# AIRZAI_BASE_BD_REVC_Sheet2.net
KiCad netlist of a schematic drawn in Altium Designer
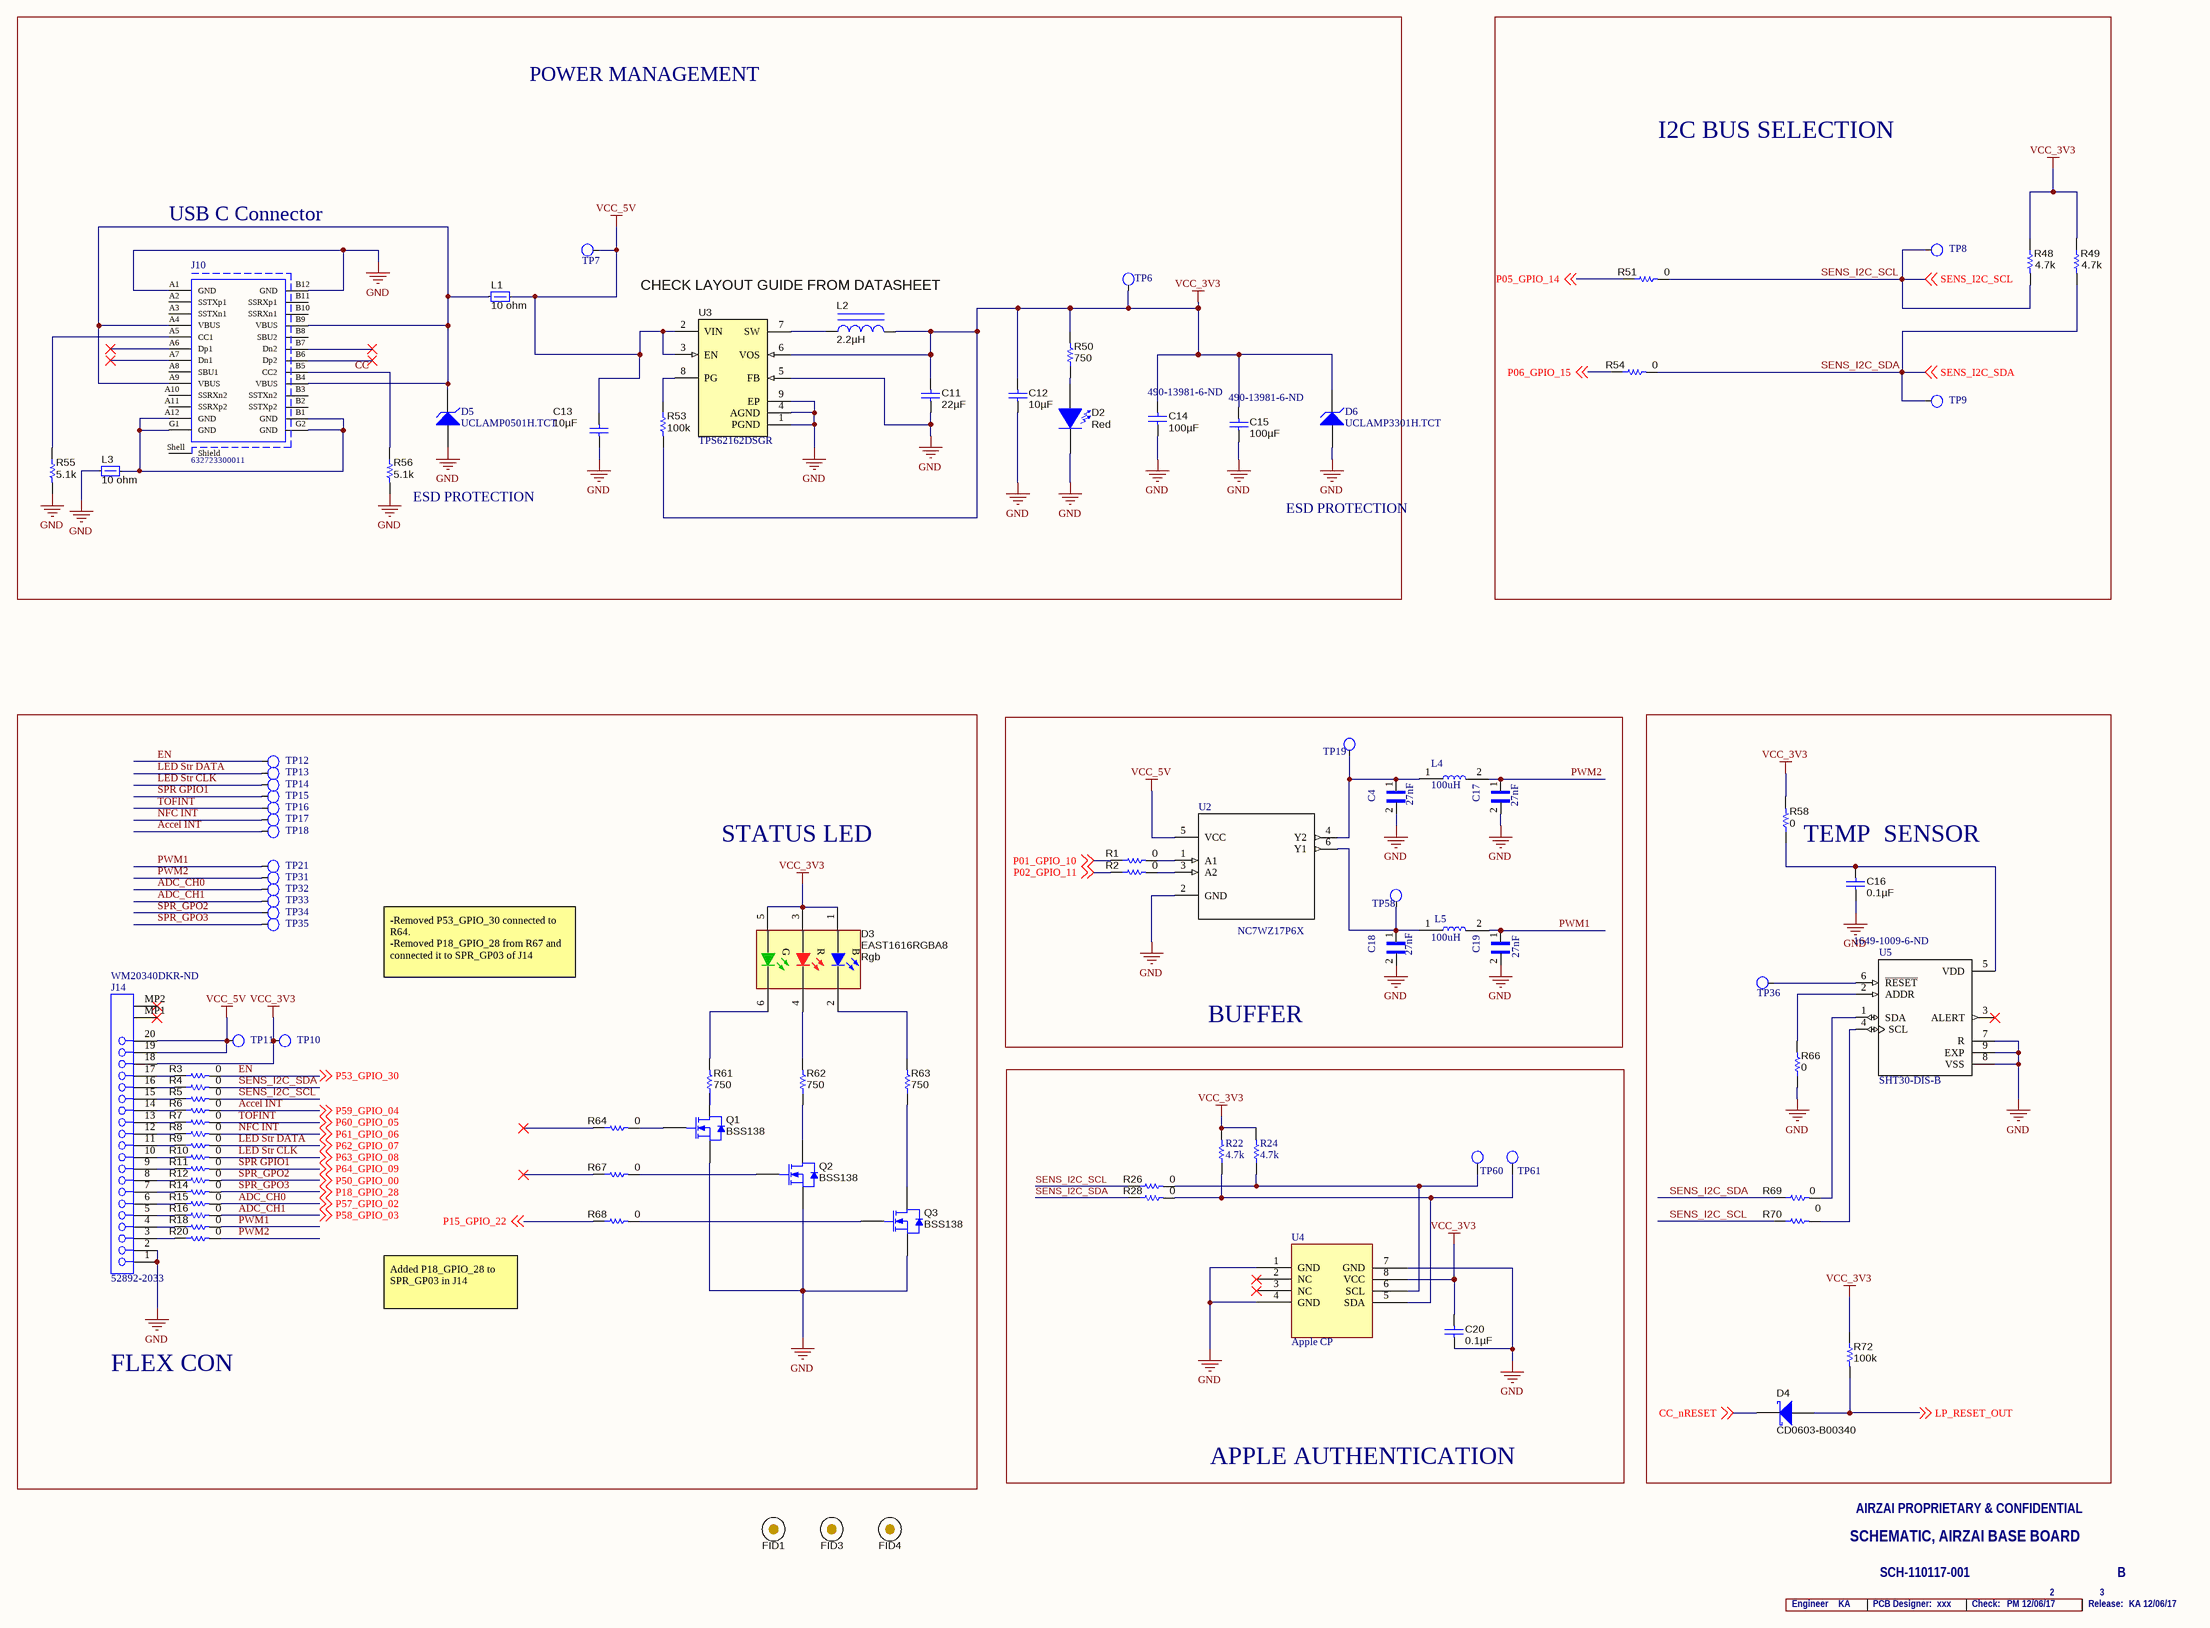
[diagram p0: AIRZAI_BASE_BD_REVC Sheet2.SchDoc]

(export (version "E")
  (design (tool "Eeschema 10.0.6"))
  (components
    (comp (ref "C4")
      (value "27nF")
      (footprint "1206CAP")
      (description "1206 27 nF 50 V Â±5% Tolerance C0G SMT Multilayer Ceramic Capacitor")
      (fields (field (name "MF") "Murata Electronics") (field (name "MP") "GRM3195C1H273JA01D"))
      (libsource (lib "GRM3195C1H273JA01D") (part "GRM3195C1H273JA01D"))
    )
    (comp (ref "C11")
      (value "C2012X5R1C226K125AC")
      (footprint "0805_HV")
      (description "CAP, CERM, 22 µF, 16 V, +/- 10%, X5R, 0805")
      (fields
        (field (name "VALUEDISPLAYED") "22µF")
        (field (name "MANUFACTURER") "TDK")
        (field (name "PUBLISHER") "Texas Instruments")
      )
      (libsource (lib "Capacitor_Ceramic") (part "C2012X5R1C226K125AC"))
    )
    (comp (ref "C12")
      (value "GRM21BR61A106KE19L")
      (footprint "0805_HV")
      (description "CAP, CERM, 10 µF, 10 V, +/- 10%, X5R, 0805")
      (fields
        (field (name "VALUEDISPLAYED") "10µF")
        (field (name "MANUFACTURER") "MuRata")
        (field (name "PUBLISHER") "Texas Instruments")
      )
      (libsource (lib "Capacitor_Ceramic") (part "GRM21BR61A106KE19L"))
    )
    (comp (ref "C13")
      (value "GRM21BR61A106KE19L")
      (footprint "0805_HV")
      (description "CAP, CERM, 10 µF, 10 V, +/- 10%, X5R, 0805")
      (fields
        (field (name "VALUEDISPLAYED") "10µF")
        (field (name "MANUFACTURER") "MuRata")
        (field (name "PUBLISHER") "Texas Instruments")
      )
      (libsource (lib "Capacitor_Ceramic") (part "GRM21BR61A106KE19L"))
    )
    (comp (ref "C14")
      (value "GRM31CR60J107ME39L")
      (footprint "1206_180")
      (description "CAP, CERM, 100 µF, 6.3 V, +/- 20%, X5R, 1206")
      (fields
        (field (name "VALUEDISPLAYED") "100µF")
        (field (name "MANUFACTURER") "MuRata")
        (field (name "SUPPLIER PART NUMBER 3") "490-13981-6-ND")
        (field (name "PUBLISHER") "Texas Instruments")
      )
      (libsource (lib "Capacitor_Ceramic") (part "GRM31CR60J107ME39L"))
    )
    (comp (ref "C15")
      (value "GRM31CR60J107ME39L")
      (footprint "1206_180")
      (description "CAP, CERM, 100 µF, 6.3 V, +/- 20%, X5R, 1206")
      (fields
        (field (name "VALUEDISPLAYED") "100µF")
        (field (name "MANUFACTURER") "MuRata")
        (field (name "SUPPLIER PART NUMBER 3") "490-13981-6-ND")
        (field (name "PUBLISHER") "Texas Instruments")
      )
      (libsource (lib "Capacitor_Ceramic") (part "GRM31CR60J107ME39L"))
    )
    (comp (ref "C16")
      (value "GRM155R61A104KA01D")
      (footprint "0402")
      (description "CAP, CERM, 0.1 µF, 10 V, +/- 10%, X5R, 0402")
      (fields
        (field (name "VALUEDISPLAYED") "0.1µF")
        (field (name "MANUFACTURER") "MuRata")
        (field (name "PUBLISHER") "Texas Instruments")
      )
      (libsource (lib "Capacitor_Ceramic") (part "GRM155R61A104KA01D"))
    )
    (comp (ref "C17")
      (value "27nF")
      (footprint "1206CAP")
      (description "1206 27 nF 50 V Â±5% Tolerance C0G SMT Multilayer Ceramic Capacitor")
      (fields (field (name "MF") "Murata Electronics") (field (name "MP") "GRM3195C1H273JA01D"))
      (libsource (lib "GRM3195C1H273JA01D") (part "GRM3195C1H273JA01D"))
    )
    (comp (ref "C18")
      (value "27nF")
      (footprint "1206CAP")
      (description "1206 27 nF 50 V Â±5% Tolerance C0G SMT Multilayer Ceramic Capacitor")
      (fields (field (name "MF") "Murata Electronics") (field (name "MP") "GRM3195C1H273JA01D"))
      (libsource (lib "GRM3195C1H273JA01D") (part "GRM3195C1H273JA01D"))
    )
    (comp (ref "C19")
      (value "27nF")
      (footprint "1206CAP")
      (description "1206 27 nF 50 V Â±5% Tolerance C0G SMT Multilayer Ceramic Capacitor")
      (fields (field (name "MF") "Murata Electronics") (field (name "MP") "GRM3195C1H273JA01D"))
      (libsource (lib "GRM3195C1H273JA01D") (part "GRM3195C1H273JA01D"))
    )
    (comp (ref "C20")
      (value "C1005X5R1A104K050BA")
      (footprint "SM0402_BTD.1SM_ACT_H55_CAP_WSS")
      (description "CAP, CERM, 0.1 µF, 10 V, +/- 10%, X5R, 0402")
      (fields
        (field (name "MANUFACTURER") "TDK")
        (field (name "VALUEDISPLAYED") "0.1µF")
        (field (name "PUBLISHER") "Texas Instruments")
      )
      (libsource (lib "AIRZAI_MBD_REVB2") (part "C1005X5R1A104K050BA"))
    )
    (comp (ref "D2")
      (value "Red")
      (footprint "SML-31_Red")
      (description "LED, Red, SMD")
      (fields
        (field (name "MANUFACTURER") "Rohm")
        (field (name "PARTNUMBER") "SML-311UTT86")
        (field (name "PUBLISHER") "Texas Instruments")
      )
      (libsource (lib "LED") (part "SML-311UTT86"))
    )
    (comp (ref "D3")
      (value "EAST1616RGBA8")
      (footprint "EAST1616_RGB")
      (description "LED, Rgb, SMD")
      (fields
        (field (name "ALTIUM_VALUE") "Rgb")
        (field (name "MANUFACTURER") "Everlight")
        (field (name "SYMBOLCREATOR") "Altium")
        (field (name "PUBLISHER") "Texas Instruments")
      )
      (libsource (lib "LED") (part "EAST1616RGBA8"))
    )
    (comp (ref "D4")
      (value "CD0603-B00340")
      (footprint "Diode_0603")
      (description "Diode, Schottky, 45 V, 0.03 A, 0603 Diode")
      (fields (field (name "MANUFACTURER") "Bourns") (field (name "PUBLISHER") "Texas Instruments"))
      (libsource (lib "Diode") (part "CD0603-B00340"))
    )
    (comp (ref "D5")
      (value "UCLAMP0501H.TCT")
      (footprint "SOD-523")
      (description "TVS DIODE 5V 12.5V SOD523")
      (fields (field (name "MANUFACTURER") "Semtech"))
      (libsource (lib "AIRZAI_BASE_BD_REVA") (part "UCLAMP0501H.TCT"))
    )
    (comp (ref "D6")
      (value "UCLAMP3301H.TCT")
      (footprint "SOD-523")
      (description "TVS DIODE 3.3V 8V SOD523")
      (fields (field (name "MANUFACTURER") "Semtech"))
      (libsource (lib "AIRZAI_BASE_BD_REVA") (part "UCLAMP3301H.TCT"))
    )
    (comp (ref "FID1")
      (value "Fiducial")
      (footprint "Fiducial10-20")
      (description "Fiducial mark.  There is nothing to buy or mount.")
      (fields (field (name "SYMBOLCREATOR") "codlsc") (field (name "PUBLISHER") "Texas Instruments"))
      (libsource (lib "MiscParts") (part "Fiducial"))
    )
    (comp (ref "FID3")
      (value "Fiducial")
      (footprint "Fiducial10-20")
      (description "Fiducial mark.  There is nothing to buy or mount.")
      (fields (field (name "SYMBOLCREATOR") "codlsc") (field (name "PUBLISHER") "Texas Instruments"))
      (libsource (lib "MiscParts") (part "Fiducial"))
    )
    (comp (ref "FID4")
      (value "Fiducial")
      (footprint "Fiducial10-20")
      (description "Fiducial mark.  There is nothing to buy or mount.")
      (fields (field (name "SYMBOLCREATOR") "codlsc") (field (name "PUBLISHER") "Texas Instruments"))
      (libsource (lib "MiscParts") (part "Fiducial"))
    )
    (comp (ref "J10")
      (value "632723300011")
      (footprint "632723300011")
      (description "USB 3.1 Type C Receptacle WR-COM, Horizontal, SMT / THT")
      (fields (field (name "PUBLISHER") "Wurth Elektronik"))
      (libsource (lib "Altium_WR-COM_USB-Connectors (rev18b)") (part "632723300011"))
    )
    (comp (ref "J14")
      (value "52892-2033")
      (footprint "MOLX-52892-2033")
      (fields (field (name "MANUFACTURER") "Molex") (field (name "SUPPLIER PART NUMBER 1") "WM20340DKR-ND"))
      (libsource (lib "Altium Content Vault") (part "MOLX-52892-2033"))
    )
    (comp (ref "L1")
      (value "10 ohm")
      (footprint "0402")
      (description "Ferrite Bead, 10 ohm @ 100 MHz, 1 A, 0402")
      (fields
        (field (name "PARTNUMBER") "BLM15AG100SN1D")
        (field (name "MANUFACTURER") "MuRata")
        (field (name "PUBLISHER") "Texas Instruments")
      )
      (libsource (lib "") (part "BLM15AG100SN1D_1"))
    )
    (comp (ref "L2")
      (value "BRC2012T2R2MD")
      (footprint "0805_HV")
      (description "Inductor, Wirewound, 2.2 µH, 1 A, 0.143 ohm, SMD")
      (fields
        (field (name "VALUEDISPLAYED") "2.2µH")
        (field (name "MANUFACTURER") "Taiyo Yuden")
        (field (name "PUBLISHER") "Texas Instruments")
      )
      (libsource (lib "Inductor_Other") (part "BRC2012T2R2MD"))
    )
    (comp (ref "L3")
      (value "10 ohm")
      (footprint "0402")
      (description "Ferrite Bead, 10 ohm @ 100 MHz, 1 A, 0402")
      (fields
        (field (name "PARTNUMBER") "BLM15AG100SN1D")
        (field (name "MANUFACTURER") "MuRata")
        (field (name "PUBLISHER") "Texas Instruments")
      )
      (libsource (lib "FerriteBead") (part "BLM15AG100SN1D"))
    )
    (comp (ref "L4")
      (value "100uH")
      (footprint "0805_Inductor")
      (description "Fixed Ind 100uh 2ma 3.1 Ohm Smd")
      (fields (field (name "MP") "MLF2012C101KTD25") (field (name "MF") "TDK"))
      (libsource (lib "MLF2012C101KTD25") (part "MLF2012C101KTD25"))
    )
    (comp (ref "L5")
      (value "100uH")
      (footprint "0805_Inductor")
      (description "Fixed Ind 100uh 2ma 3.1 Ohm Smd")
      (fields (field (name "MP") "MLF2012C101KTD25") (field (name "MF") "TDK"))
      (libsource (lib "MLF2012C101KTD25") (part "MLF2012C101KTD25"))
    )
    (comp (ref "Q1")
      (value "BSS138")
      (footprint "SOT-23")
      (description "MOSFET, N-CH, 50 V, 0.22 A, SOT-23")
      (fields
        (field (name "MANUFACTURER") "Fairchild Semiconductor")
        (field (name "PUBLISHER") "Texas Instruments")
      )
      (libsource (lib "FETs") (part "BSS138"))
    )
    (comp (ref "Q2")
      (value "BSS138")
      (footprint "SOT-23")
      (description "MOSFET, N-CH, 50 V, 0.22 A, SOT-23")
      (fields
        (field (name "MANUFACTURER") "Fairchild Semiconductor")
        (field (name "PUBLISHER") "Texas Instruments")
      )
      (libsource (lib "FETs") (part "BSS138"))
    )
    (comp (ref "Q3")
      (value "BSS138")
      (footprint "SOT-23")
      (description "MOSFET, N-CH, 50 V, 0.22 A, SOT-23")
      (fields
        (field (name "MANUFACTURER") "Fairchild Semiconductor")
        (field (name "PUBLISHER") "Texas Instruments")
      )
      (libsource (lib "FETs") (part "BSS138"))
    )
    (comp (ref "R1")
      (value "ERJ-2GE0R00X")
      (footprint "0402")
      (description "RES, 0, 5%, 0.063 W, 0402")
      (fields
        (field (name "VALUEDISPLAYED") "0")
        (field (name "MANUFACTURER") "Panasonic")
        (field (name "DIGI-KEY_PART_NUMBER") "P0.0JCT-ND")
        (field (name "PUBLISHER") "Texas Instruments")
      )
      (libsource (lib "Resistor_0402") (part "ERJ-2GE0R00X"))
    )
    (comp (ref "R2")
      (value "ERJ-2GE0R00X")
      (footprint "0402")
      (description "RES, 0, 5%, 0.063 W, 0402")
      (fields
        (field (name "VALUEDISPLAYED") "0")
        (field (name "MANUFACTURER") "Panasonic")
        (field (name "DIGI-KEY_PART_NUMBER") "P0.0JCT-ND")
        (field (name "PUBLISHER") "Texas Instruments")
      )
      (libsource (lib "Resistor_0402") (part "ERJ-2GE0R00X"))
    )
    (comp (ref "R3")
      (value "ERJ-2GE0R00X")
      (footprint "0402")
      (description "RES, 0, 5%, 0.063 W, 0402")
      (fields
        (field (name "VALUEDISPLAYED") "0")
        (field (name "MANUFACTURER") "Panasonic")
        (field (name "PUBLISHER") "Texas Instruments")
      )
      (libsource (lib "Resistor_0402") (part "ERJ-2GE0R00X"))
    )
    (comp (ref "R4")
      (value "ERJ-2GE0R00X")
      (footprint "0402")
      (description "RES, 0, 5%, 0.063 W, 0402")
      (fields
        (field (name "VALUEDISPLAYED") "0")
        (field (name "MANUFACTURER") "Panasonic")
        (field (name "PUBLISHER") "Texas Instruments")
      )
      (libsource (lib "Resistor_0402") (part "ERJ-2GE0R00X"))
    )
    (comp (ref "R5")
      (value "ERJ-2GE0R00X")
      (footprint "0402")
      (description "RES, 0, 5%, 0.063 W, 0402")
      (fields
        (field (name "VALUEDISPLAYED") "0")
        (field (name "MANUFACTURER") "Panasonic")
        (field (name "PUBLISHER") "Texas Instruments")
      )
      (libsource (lib "Resistor_0402") (part "ERJ-2GE0R00X"))
    )
    (comp (ref "R6")
      (value "ERJ-2GE0R00X")
      (footprint "0402")
      (description "RES, 0, 5%, 0.063 W, 0402")
      (fields
        (field (name "VALUEDISPLAYED") "0")
        (field (name "MANUFACTURER") "Panasonic")
        (field (name "PUBLISHER") "Texas Instruments")
      )
      (libsource (lib "Resistor_0402") (part "ERJ-2GE0R00X"))
    )
    (comp (ref "R7")
      (value "ERJ-2GE0R00X")
      (footprint "0402")
      (description "RES, 0, 5%, 0.063 W, 0402")
      (fields
        (field (name "VALUEDISPLAYED") "0")
        (field (name "MANUFACTURER") "Panasonic")
        (field (name "PUBLISHER") "Texas Instruments")
      )
      (libsource (lib "Resistor_0402") (part "ERJ-2GE0R00X"))
    )
    (comp (ref "R8")
      (value "ERJ-2GE0R00X")
      (footprint "0402")
      (description "RES, 0, 5%, 0.063 W, 0402")
      (fields
        (field (name "VALUEDISPLAYED") "0")
        (field (name "MANUFACTURER") "Panasonic")
        (field (name "PUBLISHER") "Texas Instruments")
      )
      (libsource (lib "Resistor_0402") (part "ERJ-2GE0R00X"))
    )
    (comp (ref "R9")
      (value "ERJ-2GE0R00X")
      (footprint "0402")
      (description "RES, 0, 5%, 0.063 W, 0402")
      (fields
        (field (name "VALUEDISPLAYED") "0")
        (field (name "MANUFACTURER") "Panasonic")
        (field (name "PUBLISHER") "Texas Instruments")
      )
      (libsource (lib "Resistor_0402") (part "ERJ-2GE0R00X"))
    )
    (comp (ref "R10")
      (value "ERJ-2GE0R00X")
      (footprint "0402")
      (description "RES, 0, 5%, 0.063 W, 0402")
      (fields
        (field (name "VALUEDISPLAYED") "0")
        (field (name "MANUFACTURER") "Panasonic")
        (field (name "PUBLISHER") "Texas Instruments")
      )
      (libsource (lib "Resistor_0402") (part "ERJ-2GE0R00X"))
    )
    (comp (ref "R11")
      (value "ERJ-2GE0R00X")
      (footprint "0402")
      (description "RES, 0, 5%, 0.063 W, 0402")
      (fields
        (field (name "VALUEDISPLAYED") "0")
        (field (name "MANUFACTURER") "Panasonic")
        (field (name "PUBLISHER") "Texas Instruments")
      )
      (libsource (lib "Resistor_0402") (part "ERJ-2GE0R00X"))
    )
    (comp (ref "R12")
      (value "ERJ-2GE0R00X")
      (footprint "0402")
      (description "RES, 0, 5%, 0.063 W, 0402")
      (fields
        (field (name "VALUEDISPLAYED") "0")
        (field (name "MANUFACTURER") "Panasonic")
        (field (name "PUBLISHER") "Texas Instruments")
      )
      (libsource (lib "Resistor_0402") (part "ERJ-2GE0R00X"))
    )
    (comp (ref "R14")
      (value "ERJ-2GE0R00X")
      (footprint "0402")
      (description "RES, 0, 5%, 0.063 W, 0402")
      (fields
        (field (name "VALUEDISPLAYED") "0")
        (field (name "MANUFACTURER") "Panasonic")
        (field (name "PUBLISHER") "Texas Instruments")
      )
      (libsource (lib "Resistor_0402") (part "ERJ-2GE0R00X"))
    )
    (comp (ref "R15")
      (value "ERJ-2GE0R00X")
      (footprint "0402")
      (description "RES, 0, 5%, 0.063 W, 0402")
      (fields
        (field (name "VALUEDISPLAYED") "0")
        (field (name "MANUFACTURER") "Panasonic")
        (field (name "PUBLISHER") "Texas Instruments")
      )
      (libsource (lib "Resistor_0402") (part "ERJ-2GE0R00X"))
    )
    (comp (ref "R16")
      (value "ERJ-2GE0R00X")
      (footprint "0402")
      (description "RES, 0, 5%, 0.063 W, 0402")
      (fields
        (field (name "VALUEDISPLAYED") "0")
        (field (name "MANUFACTURER") "Panasonic")
        (field (name "PUBLISHER") "Texas Instruments")
      )
      (libsource (lib "Resistor_0402") (part "ERJ-2GE0R00X"))
    )
    (comp (ref "R18")
      (value "ERJ-2GE0R00X")
      (footprint "0402")
      (description "RES, 0, 5%, 0.063 W, 0402")
      (fields
        (field (name "VALUEDISPLAYED") "0")
        (field (name "MANUFACTURER") "Panasonic")
        (field (name "PUBLISHER") "Texas Instruments")
      )
      (libsource (lib "Resistor_0402") (part "ERJ-2GE0R00X"))
    )
    (comp (ref "R20")
      (value "ERJ-2GE0R00X")
      (footprint "0402")
      (description "RES, 0, 5%, 0.063 W, 0402")
      (fields
        (field (name "VALUEDISPLAYED") "0")
        (field (name "MANUFACTURER") "Panasonic")
        (field (name "PUBLISHER") "Texas Instruments")
      )
      (libsource (lib "Resistor_0402") (part "ERJ-2GE0R00X"))
    )
    (comp (ref "R22")
      (value "RMCF0402JT4K70")
      (footprint "0402")
      (description "Chip Resistor, 4.7 KOhm, +/- 5%, 0.063 W, -55 to 155 degC, 0402 (1005 Metric), RoHS, Tape and Reel")
      (fields
        (field (name "MANUFACTURER") "Stackpole-Electronics-Inc.")
        (field (name "TOLERANCE") "±5%")
        (field (name "RESISTANCE (OHMS)") "4.7k")
      )
      (libsource (lib "AIRZAI_BASE_BD_REVA") (part "RES-2"))
    )
    (comp (ref "R24")
      (value "RMCF0402JT4K70")
      (footprint "0402")
      (description "Chip Resistor, 4.7 KOhm, +/- 5%, 0.063 W, -55 to 155 degC, 0402 (1005 Metric), RoHS, Tape and Reel")
      (fields
        (field (name "MANUFACTURER") "Stackpole-Electronics-Inc.")
        (field (name "TOLERANCE") "±5%")
        (field (name "RESISTANCE (OHMS)") "4.7k")
      )
      (libsource (lib "AIRZAI_BASE_BD_REVA") (part "RES-2"))
    )
    (comp (ref "R26")
      (value "ERJ-2GE0R00X")
      (footprint "0402")
      (description "RES, 0, 5%, 0.063 W, 0402")
      (fields
        (field (name "VALUEDISPLAYED") "0")
        (field (name "MANUFACTURER") "Panasonic")
        (field (name "DIGI-KEY_PART_NUMBER") "P0.0JCT-ND")
        (field (name "PUBLISHER") "Texas Instruments")
      )
      (libsource (lib "Resistor_0402") (part "ERJ-2GE0R00X"))
    )
    (comp (ref "R28")
      (value "ERJ-2GE0R00X")
      (footprint "0402")
      (description "RES, 0, 5%, 0.063 W, 0402")
      (fields
        (field (name "VALUEDISPLAYED") "0")
        (field (name "MANUFACTURER") "Panasonic")
        (field (name "DIGI-KEY_PART_NUMBER") "P0.0JCT-ND")
        (field (name "PUBLISHER") "Texas Instruments")
      )
      (libsource (lib "Resistor_0402") (part "ERJ-2GE0R00X"))
    )
    (comp (ref "R48")
      (value "4.7k")
      (footprint "0402")
      (description "RES SMD 4.7K OHM 1% 1/16W 0402")
      (fields
        (field (name "MANUFACTURER") "Yageo")
        (field (name "MANUFACTURER PART NUMBER") "RC0402FR-074K7L")
      )
      (libsource (lib "Resistor_0402") (part "CRCW04023K30JNED"))
    )
    (comp (ref "R49")
      (value "4.7k")
      (footprint "0402")
      (description "RES SMD 4.7K OHM 1% 1/16W 0402")
      (fields
        (field (name "MANUFACTURER") "Yageo")
        (field (name "MANUFACTURER PART NUMBER") "RC0402FR-074K7L")
      )
      (libsource (lib "Resistor_0402") (part "CRCW04023K30JNED"))
    )
    (comp (ref "R50")
      (value "RC0603JR-07750RL")
      (footprint "0603")
      (description "RES, 750, 5%, 0.1 W, 0603")
      (fields
        (field (name "VALUEDISPLAYED") "750")
        (field (name "MANUFACTURER") "Yageo America")
        (field (name "PUBLISHER") "Texas Instruments")
      )
      (libsource (lib "Resistor_0603") (part "RC0603JR-07750RL"))
    )
    (comp (ref "R51")
      (value "ERJ-2GE0R00X")
      (footprint "0402")
      (description "RES, 0, 5%, 0.063 W, 0402")
      (fields
        (field (name "VALUEDISPLAYED") "0")
        (field (name "MANUFACTURER") "Panasonic")
        (field (name "PUBLISHER") "Texas Instruments")
      )
      (libsource (lib "Resistor_0402") (part "ERJ-2GE0R00X"))
    )
    (comp (ref "R53")
      (value "CRCW0402100KJNED")
      (footprint "0402")
      (description "RES, 100 k, 5%, 0.063 W, 0402")
      (fields
        (field (name "VALUEDISPLAYED") "100k")
        (field (name "MANUFACTURER") "Vishay-Dale")
        (field (name "PUBLISHER") "Texas Instruments")
      )
      (libsource (lib "Resistor_0402") (part "CRCW0402100KJNED"))
    )
    (comp (ref "R54")
      (value "ERJ-2GE0R00X")
      (footprint "0402")
      (description "RES, 0, 5%, 0.063 W, 0402")
      (fields
        (field (name "VALUEDISPLAYED") "0")
        (field (name "MANUFACTURER") "Panasonic")
        (field (name "PUBLISHER") "Texas Instruments")
      )
      (libsource (lib "Resistor_0402") (part "ERJ-2GE0R00X"))
    )
    (comp (ref "R55")
      (value "CRCW040210K0JNED")
      (footprint "0402")
      (description "RES, 10 k, 5%, 0.063 W, 0402")
      (fields
        (field (name "VALUEDISPLAYED") "5.1k")
        (field (name "MANUFACTURER") "Vishay-Dale")
        (field (name "PUBLISHER") "Texas Instruments")
      )
      (libsource (lib "Resistor_0402") (part "CRCW040210K0JNED"))
    )
    (comp (ref "R56")
      (value "CRCW040210K0JNED")
      (footprint "0402")
      (description "RES, 10 k, 5%, 0.063 W, 0402")
      (fields
        (field (name "VALUEDISPLAYED") "5.1k")
        (field (name "MANUFACTURER") "Vishay-Dale")
        (field (name "PUBLISHER") "Texas Instruments")
      )
      (libsource (lib "Resistor_0402") (part "CRCW040210K0JNED"))
    )
    (comp (ref "R58")
      (value "ERJ-2GE0R00X")
      (footprint "0402")
      (description "RES, 0, 5%, 0.063 W, 0402")
      (fields
        (field (name "VALUEDISPLAYED") "0")
        (field (name "MANUFACTURER") "Panasonic")
        (field (name "PUBLISHER") "Texas Instruments")
      )
      (libsource (lib "Resistor_0402") (part "ERJ-2GE0R00X"))
    )
    (comp (ref "R61")
      (value "RC0603JR-07750RL")
      (footprint "0603")
      (description "RES, 750, 5%, 0.1 W, 0603")
      (fields
        (field (name "VALUEDISPLAYED") "750")
        (field (name "MANUFACTURER") "Yageo America")
        (field (name "PUBLISHER") "Texas Instruments")
      )
      (libsource (lib "Resistor_0603") (part "RC0603JR-07750RL"))
    )
    (comp (ref "R62")
      (value "RC0603JR-07750RL")
      (footprint "0603")
      (description "RES, 750, 5%, 0.1 W, 0603")
      (fields
        (field (name "VALUEDISPLAYED") "750")
        (field (name "MANUFACTURER") "Yageo America")
        (field (name "PUBLISHER") "Texas Instruments")
      )
      (libsource (lib "Resistor_0603") (part "RC0603JR-07750RL"))
    )
    (comp (ref "R63")
      (value "RC0603JR-07750RL")
      (footprint "0603")
      (description "RES, 750, 5%, 0.1 W, 0603")
      (fields
        (field (name "VALUEDISPLAYED") "750")
        (field (name "MANUFACTURER") "Yageo America")
        (field (name "PUBLISHER") "Texas Instruments")
      )
      (libsource (lib "Resistor_0603") (part "RC0603JR-07750RL"))
    )
    (comp (ref "R64")
      (value "ERJ-2GE0R00X")
      (footprint "0402")
      (description "RES, 0, 5%, 0.063 W, 0402")
      (fields
        (field (name "VALUEDISPLAYED") "0")
        (field (name "MANUFACTURER") "Panasonic")
        (field (name "PUBLISHER") "Texas Instruments")
      )
      (libsource (lib "Resistor_0402") (part "ERJ-2GE0R00X"))
    )
    (comp (ref "R66")
      (value "ERJ-2GE0R00X")
      (footprint "0402")
      (description "RES, 0, 5%, 0.063 W, 0402")
      (fields
        (field (name "VALUEDISPLAYED") "0")
        (field (name "MANUFACTURER") "Panasonic")
        (field (name "PUBLISHER") "Texas Instruments")
      )
      (libsource (lib "Resistor_0402") (part "ERJ-2GE0R00X"))
    )
    (comp (ref "R67")
      (value "ERJ-2GE0R00X")
      (footprint "0402")
      (description "RES, 0, 5%, 0.063 W, 0402")
      (fields
        (field (name "VALUEDISPLAYED") "0")
        (field (name "MANUFACTURER") "Panasonic")
        (field (name "PUBLISHER") "Texas Instruments")
      )
      (libsource (lib "Resistor_0402") (part "ERJ-2GE0R00X"))
    )
    (comp (ref "R68")
      (value "ERJ-2GE0R00X")
      (footprint "0402")
      (description "RES, 0, 5%, 0.063 W, 0402")
      (fields
        (field (name "VALUEDISPLAYED") "0")
        (field (name "MANUFACTURER") "Panasonic")
        (field (name "PUBLISHER") "Texas Instruments")
      )
      (libsource (lib "Resistor_0402") (part "ERJ-2GE0R00X"))
    )
    (comp (ref "R69")
      (value "ERJ-2GE0R00X")
      (footprint "0402")
      (description "RES, 0, 5%, 0.063 W, 0402")
      (fields
        (field (name "VALUEDISPLAYED") "0")
        (field (name "MANUFACTURER") "Panasonic")
        (field (name "PUBLISHER") "Texas Instruments")
      )
      (libsource (lib "Resistor_0402") (part "ERJ-2GE0R00X"))
    )
    (comp (ref "R70")
      (value "ERJ-2GE0R00X")
      (footprint "0402")
      (description "RES, 0, 5%, 0.063 W, 0402")
      (fields
        (field (name "VALUEDISPLAYED") "0")
        (field (name "MANUFACTURER") "Panasonic")
        (field (name "PUBLISHER") "Texas Instruments")
      )
      (libsource (lib "Resistor_0402") (part "ERJ-2GE0R00X"))
    )
    (comp (ref "R72")
      (value "CRCW0402100KJNED")
      (footprint "0402")
      (description "RES, 100 k, 5%, 0.063 W, 0402")
      (fields
        (field (name "VALUEDISPLAYED") "100k")
        (field (name "MANUFACTURER") "Vishay-Dale")
        (field (name "PUBLISHER") "Texas Instruments")
      )
      (libsource (lib "Resistor_0402") (part "CRCW0402100KJNED"))
    )
    (comp (ref "TP6")
      (value "WIREPT")
      (footprint "TP_0.9MM")
      (libsource (lib "EAGLE_CAD_Library") (part "WIREPT"))
    )
    (comp (ref "TP7")
      (value "WIREPT")
      (footprint "TP_0.9MM")
      (libsource (lib "EAGLE_CAD_Library") (part "WIREPT"))
    )
    (comp (ref "TP8")
      (value "WIREPT")
      (footprint "TP_0.9MM")
      (libsource (lib "EAGLE_CAD_Library") (part "WIREPT"))
    )
    (comp (ref "TP9")
      (value "WIREPT")
      (footprint "TP_0.9MM")
      (libsource (lib "EAGLE_CAD_Library") (part "WIREPT"))
    )
    (comp (ref "TP10")
      (value "WIREPT")
      (footprint "TP_0.9MM")
      (libsource (lib "EAGLE_CAD_Library") (part "WIREPT"))
    )
    (comp (ref "TP11")
      (value "WIREPT")
      (footprint "TP_0.9MM")
      (libsource (lib "EAGLE_CAD_Library") (part "WIREPT"))
    )
    (comp (ref "TP12")
      (value "WIREPT")
      (footprint "TP_0.9MM")
      (libsource (lib "EAGLE_CAD_Library") (part "WIREPT"))
    )
    (comp (ref "TP13")
      (value "WIREPT")
      (footprint "TP_0.9MM")
      (libsource (lib "EAGLE_CAD_Library") (part "WIREPT"))
    )
    (comp (ref "TP14")
      (value "WIREPT")
      (footprint "TP_0.9MM")
      (libsource (lib "EAGLE_CAD_Library") (part "WIREPT"))
    )
    (comp (ref "TP15")
      (value "WIREPT")
      (footprint "TP_0.9MM")
      (libsource (lib "EAGLE_CAD_Library") (part "WIREPT"))
    )
    (comp (ref "TP16")
      (value "WIREPT")
      (footprint "TP_0.9MM")
      (libsource (lib "EAGLE_CAD_Library") (part "WIREPT"))
    )
    (comp (ref "TP17")
      (value "WIREPT")
      (footprint "TP_0.9MM")
      (libsource (lib "EAGLE_CAD_Library") (part "WIREPT"))
    )
    (comp (ref "TP18")
      (value "WIREPT")
      (footprint "TP_0.9MM")
      (libsource (lib "EAGLE_CAD_Library") (part "WIREPT"))
    )
    (comp (ref "TP19")
      (value "WIREPT")
      (footprint "TP_0.9MM")
      (libsource (lib "AIRZAI_MBD_REVB") (part "WIREPT"))
    )
    (comp (ref "TP21")
      (value "WIREPT")
      (footprint "TP_0.9MM")
      (libsource (lib "EAGLE_CAD_Library") (part "WIREPT"))
    )
    (comp (ref "TP31")
      (value "WIREPT")
      (footprint "TP_0.9MM")
      (libsource (lib "EAGLE_CAD_Library") (part "WIREPT"))
    )
    (comp (ref "TP32")
      (value "WIREPT")
      (footprint "TP_0.9MM")
      (libsource (lib "EAGLE_CAD_Library") (part "WIREPT"))
    )
    (comp (ref "TP33")
      (value "WIREPT")
      (footprint "TP_0.9MM")
      (libsource (lib "EAGLE_CAD_Library") (part "WIREPT"))
    )
    (comp (ref "TP34")
      (value "WIREPT")
      (footprint "TP_0.9MM")
      (libsource (lib "EAGLE_CAD_Library") (part "WIREPT"))
    )
    (comp (ref "TP35")
      (value "WIREPT")
      (footprint "TP_0.9MM")
      (libsource (lib "EAGLE_CAD_Library") (part "WIREPT"))
    )
    (comp (ref "TP36")
      (value "WIREPT")
      (footprint "TP_0.9MM")
      (libsource (lib "EAGLE_CAD_Library") (part "WIREPT"))
    )
    (comp (ref "TP58")
      (value "WIREPT")
      (footprint "TP_0.9MM")
      (libsource (lib "AIRZAI_MBD_REVB") (part "WIREPT"))
    )
    (comp (ref "TP60")
      (value "TESTPOINT")
      (footprint "TP_0.9MM")
      (libsource (lib "AIRZAI_LID_BD_REVA") (part "TESTPOINT"))
    )
    (comp (ref "TP61")
      (value "TESTPOINT")
      (footprint "TP_0.9MM")
      (libsource (lib "AIRZAI_LID_BD_REVA") (part "TESTPOINT"))
    )
    (comp (ref "U2")
      (value "NC7WZ17P6X")
      (footprint "SC-70-NC7WZ17P6X")
      (description "NC7WZ17 Series 5.5 V TinyLogic UHS Dual Buffer w/ Schmitt Trigger Inputs-SC-70-6")
      (fields (field (name "MF") "ON Semiconductor"))
      (libsource (lib "NC7WZ17P6X") (part "NC7WZ17P6X"))
    )
    (comp (ref "U3")
      (value "TPS62162DSGR")
      (footprint "DSG0008A")
      (fields
        (field (name "MANUFACTURER") "Texas Instruments")
        (field (name "ALTERNATE PARTNUMBER") "Equivalent")
      )
      (libsource (lib "TI Power Management Step-Down Regulator") (part "TPS62162DSGR"))
    )
    (comp (ref "U4")
      (value "Apple CP")
      (footprint "XDFN-8P-Apple")
      (description "Auth 3.0 CP")
      (fields (field (name "MP") "MFI343S00177") (field (name "MF") "Apple"))
      (libsource (lib "MFI337S3959") (part "Apple CP"))
    )
    (comp (ref "U5")
      (value "SHT30-DIS-B")
      (footprint "DFN250X250X100-9N")
      (description "SHT3x Series 5.5 V Â±3 %RH 0 to 100% Temperature and Humidity Sensor - DFN-8")
      (fields (field (name "MF") "Sensirion AG") (field (name "SUPPLIER PART NUMBER 1") "1649-1009-6-ND"))
      (libsource (lib "SHT30-DIS-B") (part "SHT30-DIS-B"))
    )
  )
  (nets
    (net (code "1") (name "/CC") (class "Default")
      (node (ref "J10") (pin "B5") (pinfunction "CC2_B5") (pintype "passive"))
      (node (ref "R56") (pin "1") (pinfunction "1_1") (pintype "passive"))
    )
    (net (code "2") (name "/PWM1") (class "Default")
      (node (ref "C19") (pin "1") (pinfunction "1_1") (pintype "passive"))
      (node (ref "L5") (pin "2") (pinfunction "2_2") (pintype "passive"))
      (node (ref "R18") (pin "2") (pinfunction "2_2") (pintype "passive"))
      (node (ref "TP21") (pin "1") (pinfunction "1_1") (pintype "passive"))
    )
    (net (code "3") (name "/PWM2") (class "Default")
      (node (ref "C17") (pin "1") (pinfunction "1_1") (pintype "passive"))
      (node (ref "L4") (pin "2") (pinfunction "2_2") (pintype "passive"))
      (node (ref "R20") (pin "2") (pinfunction "2_2") (pintype "passive"))
      (node (ref "TP31") (pin "1") (pinfunction "1_1") (pintype "passive"))
    )
    (net (code "4") (name "CC_nRESET") (class "Default")
      (node (ref "D4") (pin "1") (pinfunction "K_1") (pintype "passive"))
    )
    (net (code "5") (name "GND") (class "Default")
      (node (ref "C11") (pin "2") (pinfunction "2_2") (pintype "passive"))
      (node (ref "C12") (pin "2") (pinfunction "2_2") (pintype "passive"))
      (node (ref "C13") (pin "2") (pinfunction "2_2") (pintype "passive"))
      (node (ref "C14") (pin "2") (pinfunction "2_2") (pintype "passive"))
      (node (ref "C15") (pin "2") (pinfunction "2_2") (pintype "passive"))
      (node (ref "C16") (pin "2") (pinfunction "2_2") (pintype "passive"))
      (node (ref "C17") (pin "2") (pinfunction "2_2") (pintype "passive"))
      (node (ref "C18") (pin "2") (pinfunction "2_2") (pintype "passive"))
      (node (ref "C19") (pin "2") (pinfunction "2_2") (pintype "passive"))
      (node (ref "C20") (pin "2") (pinfunction "2_2") (pintype "passive"))
      (node (ref "C4") (pin "2") (pinfunction "2_2") (pintype "passive"))
      (node (ref "D2") (pin "1") (pinfunction "K_1") (pintype "passive"))
      (node (ref "D5") (pin "A") (pinfunction "A_A") (pintype "passive"))
      (node (ref "D6") (pin "A") (pinfunction "A_A") (pintype "passive"))
      (node (ref "J10") (pin "A1") (pinfunction "GND_A1") (pintype "passive"))
      (node (ref "J10") (pin "B12") (pinfunction "GND_B12") (pintype "passive"))
      (node (ref "J14") (pin "1") (pinfunction "1_1") (pintype "passive"))
      (node (ref "J14") (pin "2") (pinfunction "2_2") (pintype "passive"))
      (node (ref "L3") (pin "2") (pinfunction "2_2") (pintype "passive"))
      (node (ref "Q1") (pin "2") (pinfunction "S_2") (pintype "passive"))
      (node (ref "Q2") (pin "2") (pinfunction "S_2") (pintype "passive"))
      (node (ref "Q3") (pin "2") (pinfunction "S_2") (pintype "passive"))
      (node (ref "R55") (pin "2") (pinfunction "2_2") (pintype "passive"))
      (node (ref "R56") (pin "2") (pinfunction "2_2") (pintype "passive"))
      (node (ref "R66") (pin "1") (pinfunction "1_1") (pintype "passive"))
      (node (ref "U2") (pin "2") (pinfunction "GND_2") (pintype "passive"))
      (node (ref "U3") (pin "1") (pinfunction "PGND_1") (pintype "power_in"))
      (node (ref "U3") (pin "4") (pinfunction "AGND_4") (pintype "power_in"))
      (node (ref "U3") (pin "5") (pinfunction "FB_5") (pintype "input"))
      (node (ref "U3") (pin "9") (pinfunction "EP_9") (pintype "power_in"))
      (node (ref "U4") (pin "1") (pinfunction "GND_1") (pintype "passive"))
      (node (ref "U4") (pin "4") (pinfunction "GND_4") (pintype "passive"))
      (node (ref "U4") (pin "7") (pinfunction "GND_7") (pintype "passive"))
      (node (ref "U5") (pin "7") (pinfunction "R_7") (pintype "passive"))
      (node (ref "U5") (pin "8") (pinfunction "VSS_8") (pintype "passive"))
      (node (ref "U5") (pin "9") (pinfunction "EXP_9") (pintype "passive"))
    )
    (net (code "6") (name "LP_RESET_OUT") (class "Default")
      (node (ref "D4") (pin "2") (pinfunction "A_2") (pintype "passive"))
      (node (ref "R72") (pin "2") (pinfunction "2_2") (pintype "passive"))
    )
    (net (code "7") (name "Net-(D2-A)") (class "Default")
      (node (ref "D2") (pin "2") (pinfunction "A_2") (pintype "passive"))
      (node (ref "R50") (pin "1") (pinfunction "1_1") (pintype "passive"))
    )
    (net (code "8") (name "Net-(D3-K-Pad2)") (class "Default")
      (node (ref "D3") (pin "2") (pinfunction "K_2") (pintype "passive"))
      (node (ref "R63") (pin "2") (pinfunction "2_2") (pintype "passive"))
    )
    (net (code "9") (name "Net-(D3-K-Pad4)") (class "Default")
      (node (ref "D3") (pin "4") (pinfunction "K_4") (pintype "passive"))
      (node (ref "R62") (pin "2") (pinfunction "2_2") (pintype "passive"))
    )
    (net (code "10") (name "Net-(D3-K-Pad6)") (class "Default")
      (node (ref "D3") (pin "6") (pinfunction "K_6") (pintype "passive"))
      (node (ref "R61") (pin "2") (pinfunction "2_2") (pintype "passive"))
    )
    (net (code "11") (name "Net-(D5-PadK)") (class "Default")
      (node (ref "D5") (pin "K") (pinfunction "K_K") (pintype "passive"))
      (node (ref "J10") (pin "A4") (pinfunction "VBUS_A4") (pintype "passive"))
      (node (ref "J10") (pin "A9") (pinfunction "VBUS_A9") (pintype "passive"))
      (node (ref "J10") (pin "B4") (pinfunction "VBUS_B4") (pintype "passive"))
      (node (ref "J10") (pin "B9") (pinfunction "VBUS_B9") (pintype "passive"))
      (node (ref "L1") (pin "1") (pinfunction "1_1") (pintype "passive"))
    )
    (net (code "12") (name "Net-(J10-CC1)") (class "Default")
      (node (ref "J10") (pin "A5") (pinfunction "CC1_A5") (pintype "passive"))
      (node (ref "R55") (pin "1") (pinfunction "1_1") (pintype "passive"))
    )
    (net (code "13") (name "Net-(J10-GND-PadA12)") (class "Default")
      (node (ref "J10") (pin "A12") (pinfunction "GND_A12") (pintype "passive"))
      (node (ref "J10") (pin "B1") (pinfunction "GND_B1") (pintype "passive"))
      (node (ref "J10") (pin "G1") (pinfunction "GND_G1") (pintype "passive"))
      (node (ref "J10") (pin "G2") (pinfunction "GND_G2") (pintype "passive"))
      (node (ref "L3") (pin "1") (pinfunction "1_1") (pintype "passive"))
    )
    (net (code "14") (name "Net-(J14-Pad3)") (class "Default")
      (node (ref "J14") (pin "3") (pinfunction "3_3") (pintype "passive"))
      (node (ref "R20") (pin "1") (pinfunction "1_1") (pintype "passive"))
    )
    (net (code "15") (name "Net-(J14-Pad4)") (class "Default")
      (node (ref "J14") (pin "4") (pinfunction "4_4") (pintype "passive"))
      (node (ref "R18") (pin "1") (pinfunction "1_1") (pintype "passive"))
    )
    (net (code "16") (name "Net-(J14-Pad5)") (class "Default")
      (node (ref "J14") (pin "5") (pinfunction "5_5") (pintype "passive"))
      (node (ref "R16") (pin "1") (pinfunction "1_1") (pintype "passive"))
    )
    (net (code "17") (name "Net-(J14-Pad6)") (class "Default")
      (node (ref "J14") (pin "6") (pinfunction "6_6") (pintype "passive"))
      (node (ref "R15") (pin "1") (pinfunction "1_1") (pintype "passive"))
    )
    (net (code "18") (name "Net-(J14-Pad7)") (class "Default")
      (node (ref "J14") (pin "7") (pinfunction "7_7") (pintype "passive"))
      (node (ref "R14") (pin "1") (pinfunction "1_1") (pintype "passive"))
    )
    (net (code "19") (name "Net-(J14-Pad8)") (class "Default")
      (node (ref "J14") (pin "8") (pinfunction "8_8") (pintype "passive"))
      (node (ref "R12") (pin "1") (pinfunction "1_1") (pintype "passive"))
    )
    (net (code "20") (name "Net-(J14-Pad9)") (class "Default")
      (node (ref "J14") (pin "9") (pinfunction "9_9") (pintype "passive"))
      (node (ref "R11") (pin "1") (pinfunction "1_1") (pintype "passive"))
    )
    (net (code "21") (name "Net-(J14-Pad10)") (class "Default")
      (node (ref "J14") (pin "10") (pinfunction "10_10") (pintype "passive"))
      (node (ref "R10") (pin "1") (pinfunction "1_1") (pintype "passive"))
    )
    (net (code "22") (name "Net-(J14-Pad11)") (class "Default")
      (node (ref "J14") (pin "11") (pinfunction "11_11") (pintype "passive"))
      (node (ref "R9") (pin "1") (pinfunction "1_1") (pintype "passive"))
    )
    (net (code "23") (name "Net-(J14-Pad12)") (class "Default")
      (node (ref "J14") (pin "12") (pinfunction "12_12") (pintype "passive"))
      (node (ref "R8") (pin "1") (pinfunction "1_1") (pintype "passive"))
    )
    (net (code "24") (name "Net-(J14-Pad13)") (class "Default")
      (node (ref "J14") (pin "13") (pinfunction "13_13") (pintype "passive"))
      (node (ref "R7") (pin "1") (pinfunction "1_1") (pintype "passive"))
    )
    (net (code "25") (name "Net-(J14-Pad14)") (class "Default")
      (node (ref "J14") (pin "14") (pinfunction "14_14") (pintype "passive"))
      (node (ref "R6") (pin "1") (pinfunction "1_1") (pintype "passive"))
    )
    (net (code "26") (name "Net-(J14-Pad15)") (class "Default")
      (node (ref "J14") (pin "15") (pinfunction "15_15") (pintype "passive"))
      (node (ref "R5") (pin "1") (pinfunction "1_1") (pintype "passive"))
    )
    (net (code "27") (name "Net-(J14-Pad16)") (class "Default")
      (node (ref "J14") (pin "16") (pinfunction "16_16") (pintype "passive"))
      (node (ref "R4") (pin "1") (pinfunction "1_1") (pintype "passive"))
    )
    (net (code "28") (name "Net-(J14-Pad17)") (class "Default")
      (node (ref "J14") (pin "17") (pinfunction "17_17") (pintype "passive"))
      (node (ref "R3") (pin "1") (pinfunction "1_1") (pintype "passive"))
    )
    (net (code "29") (name "Net-(Q1-D)") (class "Default")
      (node (ref "Q1") (pin "3") (pinfunction "D_3") (pintype "passive"))
      (node (ref "R61") (pin "1") (pinfunction "1_1") (pintype "passive"))
    )
    (net (code "30") (name "Net-(Q1-G)") (class "Default")
      (node (ref "Q1") (pin "1") (pinfunction "G_1") (pintype "passive"))
      (node (ref "R64") (pin "2") (pinfunction "2_2") (pintype "passive"))
    )
    (net (code "31") (name "Net-(Q2-D)") (class "Default")
      (node (ref "Q2") (pin "3") (pinfunction "D_3") (pintype "passive"))
      (node (ref "R62") (pin "1") (pinfunction "1_1") (pintype "passive"))
    )
    (net (code "32") (name "Net-(Q2-G)") (class "Default")
      (node (ref "Q2") (pin "1") (pinfunction "G_1") (pintype "passive"))
      (node (ref "R67") (pin "2") (pinfunction "2_2") (pintype "passive"))
    )
    (net (code "33") (name "Net-(Q3-D)") (class "Default")
      (node (ref "Q3") (pin "3") (pinfunction "D_3") (pintype "passive"))
      (node (ref "R63") (pin "1") (pinfunction "1_1") (pintype "passive"))
    )
    (net (code "34") (name "Net-(Q3-G)") (class "Default")
      (node (ref "Q3") (pin "1") (pinfunction "G_1") (pintype "passive"))
      (node (ref "R68") (pin "2") (pinfunction "2_2") (pintype "passive"))
    )
    (net (code "35") (name "Net-(U2-A1)") (class "Default")
      (node (ref "R1") (pin "2") (pinfunction "2_2") (pintype "passive"))
      (node (ref "U2") (pin "1") (pinfunction "A1_1") (pintype "input"))
    )
    (net (code "36") (name "Net-(U2-A2)") (class "Default")
      (node (ref "R2") (pin "2") (pinfunction "2_2") (pintype "passive"))
      (node (ref "U2") (pin "3") (pinfunction "A2_3") (pintype "input"))
    )
    (net (code "37") (name "Net-(U2-Y1)") (class "Default")
      (node (ref "C18") (pin "1") (pinfunction "1_1") (pintype "passive"))
      (node (ref "L5") (pin "1") (pinfunction "1_1") (pintype "passive"))
      (node (ref "TP58") (pin "1") (pinfunction "1_1") (pintype "passive"))
      (node (ref "U2") (pin "6") (pinfunction "Y1_6") (pintype "output"))
    )
    (net (code "38") (name "Net-(U2-Y2)") (class "Default")
      (node (ref "C4") (pin "1") (pinfunction "1_1") (pintype "passive"))
      (node (ref "L4") (pin "1") (pinfunction "1_1") (pintype "passive"))
      (node (ref "TP19") (pin "1") (pinfunction "1_1") (pintype "passive"))
      (node (ref "U2") (pin "4") (pinfunction "Y2_4") (pintype "output"))
    )
    (net (code "39") (name "Net-(U3-PG)") (class "Default")
      (node (ref "R53") (pin "1") (pinfunction "1_1") (pintype "passive"))
      (node (ref "U3") (pin "8") (pinfunction "PG_8") (pintype "tri_state"))
    )
    (net (code "40") (name "Net-(U3-SW)") (class "Default")
      (node (ref "L2") (pin "1") (pinfunction "1_1") (pintype "passive"))
      (node (ref "U3") (pin "7") (pinfunction "SW_7") (pintype "power_in"))
    )
    (net (code "41") (name "Net-(U4-SCL)") (class "Default")
      (node (ref "R24") (pin "1") (pinfunction "1_1") (pintype "passive"))
      (node (ref "R26") (pin "2") (pinfunction "2_2") (pintype "passive"))
      (node (ref "TP60") (pin "1") (pinfunction "1_1") (pintype "passive"))
      (node (ref "U4") (pin "6") (pinfunction "SCL_6") (pintype "passive"))
    )
    (net (code "42") (name "Net-(U4-SDA)") (class "Default")
      (node (ref "R22") (pin "1") (pinfunction "1_1") (pintype "passive"))
      (node (ref "R28") (pin "2") (pinfunction "2_2") (pintype "passive"))
      (node (ref "TP61") (pin "1") (pinfunction "1_1") (pintype "passive"))
      (node (ref "U4") (pin "5") (pinfunction "SDA_5") (pintype "passive"))
    )
    (net (code "43") (name "Net-(U5-ADDR)") (class "Default")
      (node (ref "R66") (pin "2") (pinfunction "2_2") (pintype "passive"))
      (node (ref "U5") (pin "2") (pinfunction "ADDR_2") (pintype "input"))
    )
    (net (code "44") (name "Net-(U5-SCL)") (class "Default")
      (node (ref "R70") (pin "2") (pinfunction "2_2") (pintype "passive"))
      (node (ref "U5") (pin "4") (pinfunction "SCL_4") (pintype "bidirectional"))
    )
    (net (code "45") (name "Net-(U5-SDA)") (class "Default")
      (node (ref "R69") (pin "2") (pinfunction "2_2") (pintype "passive"))
      (node (ref "U5") (pin "1") (pinfunction "SDA_1") (pintype "bidirectional"))
    )
    (net (code "46") (name "Net-(U5-VDD)") (class "Default")
      (node (ref "C16") (pin "1") (pinfunction "1_1") (pintype "passive"))
      (node (ref "R58") (pin "1") (pinfunction "1_1") (pintype "passive"))
      (node (ref "U5") (pin "5") (pinfunction "VDD_5") (pintype "power_in"))
    )
    (net (code "47") (name "Net-(U5-~{RESET})") (class "Default")
      (node (ref "TP36") (pin "1") (pinfunction "1_1") (pintype "passive"))
      (node (ref "U5") (pin "6") (pinfunction "~{RESET}_6") (pintype "input"))
    )
    (net (code "48") (name "P01_GPIO_10") (class "Default")
      (node (ref "R1") (pin "1") (pinfunction "1_1") (pintype "passive"))
    )
    (net (code "49") (name "P02_GPIO_11") (class "Default")
      (node (ref "R2") (pin "1") (pinfunction "1_1") (pintype "passive"))
    )
    (net (code "50") (name "P05_GPIO_14") (class "Default")
      (node (ref "R51") (pin "1") (pinfunction "1_1") (pintype "passive"))
    )
    (net (code "51") (name "P06_GPIO_15") (class "Default")
      (node (ref "R54") (pin "1") (pinfunction "1_1") (pintype "passive"))
    )
    (net (code "52") (name "P15_GPIO_22") (class "Default")
      (node (ref "R68") (pin "1") (pinfunction "1_1") (pintype "passive"))
    )
    (net (code "53") (name "P18_GPIO_28") (class "Default")
      (node (ref "R14") (pin "2") (pinfunction "2_2") (pintype "passive"))
      (node (ref "TP35") (pin "1") (pinfunction "1_1") (pintype "passive"))
    )
    (net (code "54") (name "P50_GPIO_00") (class "Default")
      (node (ref "R12") (pin "2") (pinfunction "2_2") (pintype "passive"))
      (node (ref "TP34") (pin "1") (pinfunction "1_1") (pintype "passive"))
    )
    (net (code "55") (name "P53_GPIO_30") (class "Default")
      (node (ref "R3") (pin "2") (pinfunction "2_2") (pintype "passive"))
      (node (ref "TP12") (pin "1") (pinfunction "1_1") (pintype "passive"))
    )
    (net (code "56") (name "P57_GPIO_02") (class "Default")
      (node (ref "R15") (pin "2") (pinfunction "2_2") (pintype "passive"))
      (node (ref "TP32") (pin "1") (pinfunction "1_1") (pintype "passive"))
    )
    (net (code "57") (name "P58_GPIO_03") (class "Default")
      (node (ref "R16") (pin "2") (pinfunction "2_2") (pintype "passive"))
      (node (ref "TP33") (pin "1") (pinfunction "1_1") (pintype "passive"))
    )
    (net (code "58") (name "P59_GPIO_04") (class "Default")
      (node (ref "R6") (pin "2") (pinfunction "2_2") (pintype "passive"))
      (node (ref "TP18") (pin "1") (pinfunction "1_1") (pintype "passive"))
    )
    (net (code "59") (name "P60_GPIO_05") (class "Default")
      (node (ref "R7") (pin "2") (pinfunction "2_2") (pintype "passive"))
      (node (ref "TP16") (pin "1") (pinfunction "1_1") (pintype "passive"))
    )
    (net (code "60") (name "P61_GPIO_06") (class "Default")
      (node (ref "R8") (pin "2") (pinfunction "2_2") (pintype "passive"))
      (node (ref "TP17") (pin "1") (pinfunction "1_1") (pintype "passive"))
    )
    (net (code "61") (name "P62_GPIO_07") (class "Default")
      (node (ref "R9") (pin "2") (pinfunction "2_2") (pintype "passive"))
      (node (ref "TP13") (pin "1") (pinfunction "1_1") (pintype "passive"))
    )
    (net (code "62") (name "P63_GPIO_08") (class "Default")
      (node (ref "R10") (pin "2") (pinfunction "2_2") (pintype "passive"))
      (node (ref "TP14") (pin "1") (pinfunction "1_1") (pintype "passive"))
    )
    (net (code "63") (name "P64_GPIO_09") (class "Default")
      (node (ref "R11") (pin "2") (pinfunction "2_2") (pintype "passive"))
      (node (ref "TP15") (pin "1") (pinfunction "1_1") (pintype "passive"))
    )
    (net (code "64") (name "SENS_I2C_SCL") (class "Default")
      (node (ref "R26") (pin "1") (pinfunction "1_1") (pintype "passive"))
      (node (ref "R48") (pin "2") (pinfunction "2_2") (pintype "passive"))
      (node (ref "R5") (pin "2") (pinfunction "2_2") (pintype "passive"))
      (node (ref "R51") (pin "2") (pinfunction "2_2") (pintype "passive"))
      (node (ref "R70") (pin "1") (pinfunction "1_1") (pintype "passive"))
      (node (ref "TP8") (pin "1") (pinfunction "1_1") (pintype "passive"))
    )
    (net (code "65") (name "SENS_I2C_SDA") (class "Default")
      (node (ref "R28") (pin "1") (pinfunction "1_1") (pintype "passive"))
      (node (ref "R4") (pin "2") (pinfunction "2_2") (pintype "passive"))
      (node (ref "R49") (pin "2") (pinfunction "2_2") (pintype "passive"))
      (node (ref "R54") (pin "2") (pinfunction "2_2") (pintype "passive"))
      (node (ref "R69") (pin "1") (pinfunction "1_1") (pintype "passive"))
      (node (ref "TP9") (pin "1") (pinfunction "1_1") (pintype "passive"))
    )
    (net (code "66") (name "VCC_3V3") (class "Default")
      (node (ref "C11") (pin "1") (pinfunction "1_1") (pintype "passive"))
      (node (ref "C12") (pin "1") (pinfunction "1_1") (pintype "passive"))
      (node (ref "C14") (pin "1") (pinfunction "1_1") (pintype "passive"))
      (node (ref "C15") (pin "1") (pinfunction "1_1") (pintype "passive"))
      (node (ref "C20") (pin "1") (pinfunction "1_1") (pintype "passive"))
      (node (ref "D3") (pin "1") (pinfunction "A_1") (pintype "passive"))
      (node (ref "D3") (pin "3") (pinfunction "A_3") (pintype "passive"))
      (node (ref "D3") (pin "5") (pinfunction "A_5") (pintype "passive"))
      (node (ref "D6") (pin "K") (pinfunction "K_K") (pintype "passive"))
      (node (ref "J14") (pin "18") (pinfunction "18_18") (pintype "passive"))
      (node (ref "L2") (pin "2") (pinfunction "2_2") (pintype "passive"))
      (node (ref "R22") (pin "2") (pinfunction "2_2") (pintype "passive"))
      (node (ref "R24") (pin "2") (pinfunction "2_2") (pintype "passive"))
      (node (ref "R48") (pin "1") (pinfunction "1_1") (pintype "passive"))
      (node (ref "R49") (pin "1") (pinfunction "1_1") (pintype "passive"))
      (node (ref "R50") (pin "2") (pinfunction "2_2") (pintype "passive"))
      (node (ref "R53") (pin "2") (pinfunction "2_2") (pintype "passive"))
      (node (ref "R58") (pin "2") (pinfunction "2_2") (pintype "passive"))
      (node (ref "R72") (pin "1") (pinfunction "1_1") (pintype "passive"))
      (node (ref "TP10") (pin "1") (pinfunction "1_1") (pintype "passive"))
      (node (ref "TP6") (pin "1") (pinfunction "1_1") (pintype "passive"))
      (node (ref "U3") (pin "6") (pinfunction "VOS_6") (pintype "input"))
      (node (ref "U4") (pin "8") (pinfunction "VCC_8") (pintype "passive"))
    )
    (net (code "67") (name "VCC_5V") (class "Default")
      (node (ref "C13") (pin "1") (pinfunction "1_1") (pintype "passive"))
      (node (ref "J14") (pin "19") (pinfunction "19_19") (pintype "passive"))
      (node (ref "J14") (pin "20") (pinfunction "20_20") (pintype "passive"))
      (node (ref "L1") (pin "2") (pinfunction "2_2") (pintype "passive"))
      (node (ref "TP11") (pin "1") (pinfunction "1_1") (pintype "passive"))
      (node (ref "TP7") (pin "1") (pinfunction "1_1") (pintype "passive"))
      (node (ref "U2") (pin "5") (pinfunction "VCC_5") (pintype "power_in"))
      (node (ref "U3") (pin "2") (pinfunction "VIN_2") (pintype "power_in"))
      (node (ref "U3") (pin "3") (pinfunction "EN_3") (pintype "input"))
    )
    (net (code "68") (name "unconnected-(J10-Dn1-PadA7)") (class "Default")
      (node (ref "J10") (pin "A7") (pinfunction "Dn1_A7") (pintype "passive+no_connect"))
    )
    (net (code "69") (name "unconnected-(J10-Dn2-PadB7)") (class "Default")
      (node (ref "J10") (pin "B7") (pinfunction "Dn2_B7") (pintype "passive+no_connect"))
    )
    (net (code "70") (name "unconnected-(J10-Dp1-PadA6)") (class "Default")
      (node (ref "J10") (pin "A6") (pinfunction "Dp1_A6") (pintype "passive+no_connect"))
    )
    (net (code "71") (name "unconnected-(J10-Dp2-PadB6)") (class "Default")
      (node (ref "J10") (pin "B6") (pinfunction "Dp2_B6") (pintype "passive+no_connect"))
    )
    (net (code "72") (name "unconnected-(J10-SBU1-PadA8)") (class "Default")
      (node (ref "J10") (pin "A8") (pinfunction "SBU1_A8") (pintype "passive"))
    )
    (net (code "73") (name "unconnected-(J10-SBU2-PadB8)") (class "Default")
      (node (ref "J10") (pin "B8") (pinfunction "SBU2_B8") (pintype "passive"))
    )
    (net (code "74") (name "unconnected-(J10-SSRXn1-PadB10)") (class "Default")
      (node (ref "J10") (pin "B10") (pinfunction "SSRXn1_B10") (pintype "passive"))
    )
    (net (code "75") (name "unconnected-(J10-SSRXn2-PadA10)") (class "Default")
      (node (ref "J10") (pin "A10") (pinfunction "SSRXn2_A10") (pintype "passive"))
    )
    (net (code "76") (name "unconnected-(J10-SSRXp1-PadB11)") (class "Default")
      (node (ref "J10") (pin "B11") (pinfunction "SSRXp1_B11") (pintype "passive"))
    )
    (net (code "77") (name "unconnected-(J10-SSRXp2-PadA11)") (class "Default")
      (node (ref "J10") (pin "A11") (pinfunction "SSRXp2_A11") (pintype "passive"))
    )
    (net (code "78") (name "unconnected-(J10-SSTXn1-PadA3)") (class "Default")
      (node (ref "J10") (pin "A3") (pinfunction "SSTXn1_A3") (pintype "passive"))
    )
    (net (code "79") (name "unconnected-(J10-SSTXn2-PadB3)") (class "Default")
      (node (ref "J10") (pin "B3") (pinfunction "SSTXn2_B3") (pintype "passive"))
    )
    (net (code "80") (name "unconnected-(J10-SSTXp1-PadA2)") (class "Default")
      (node (ref "J10") (pin "A2") (pinfunction "SSTXp1_A2") (pintype "passive"))
    )
    (net (code "81") (name "unconnected-(J10-SSTXp2-PadB2)") (class "Default")
      (node (ref "J10") (pin "B2") (pinfunction "SSTXp2_B2") (pintype "passive"))
    )
    (net (code "82") (name "unconnected-(J10-Shield-PadShell)") (class "Default")
      (node (ref "J10") (pin "Shell") (pinfunction "Shield_Shell") (pintype "passive"))
    )
    (net (code "83") (name "unconnected-(J14-PadMP1)") (class "Default")
      (node (ref "J14") (pin "MP1") (pinfunction "MP1_MP1") (pintype "passive+no_connect"))
    )
    (net (code "84") (name "unconnected-(J14-PadMP2)") (class "Default")
      (node (ref "J14") (pin "MP2") (pinfunction "MP2_MP2") (pintype "passive+no_connect"))
    )
    (net (code "85") (name "unconnected-(R64-Pad1)") (class "Default")
      (node (ref "R64") (pin "1") (pinfunction "1_1") (pintype "passive+no_connect"))
    )
    (net (code "86") (name "unconnected-(R67-Pad1)") (class "Default")
      (node (ref "R67") (pin "1") (pinfunction "1_1") (pintype "passive+no_connect"))
    )
    (net (code "87") (name "unconnected-(U4-NC-Pad2)") (class "Default")
      (node (ref "U4") (pin "2") (pinfunction "NC_2") (pintype "passive+no_connect"))
    )
    (net (code "88") (name "unconnected-(U4-NC-Pad3)") (class "Default")
      (node (ref "U4") (pin "3") (pinfunction "NC_3") (pintype "passive+no_connect"))
    )
    (net (code "89") (name "unconnected-(U5-ALERT-Pad3)") (class "Default")
      (node (ref "U5") (pin "3") (pinfunction "ALERT_3") (pintype "output+no_connect"))
    )
  )
)
